# pCog100_Wifi_Sensor_uSD_TFT.net
KiCad netlist of a schematic drawn in EAGLE
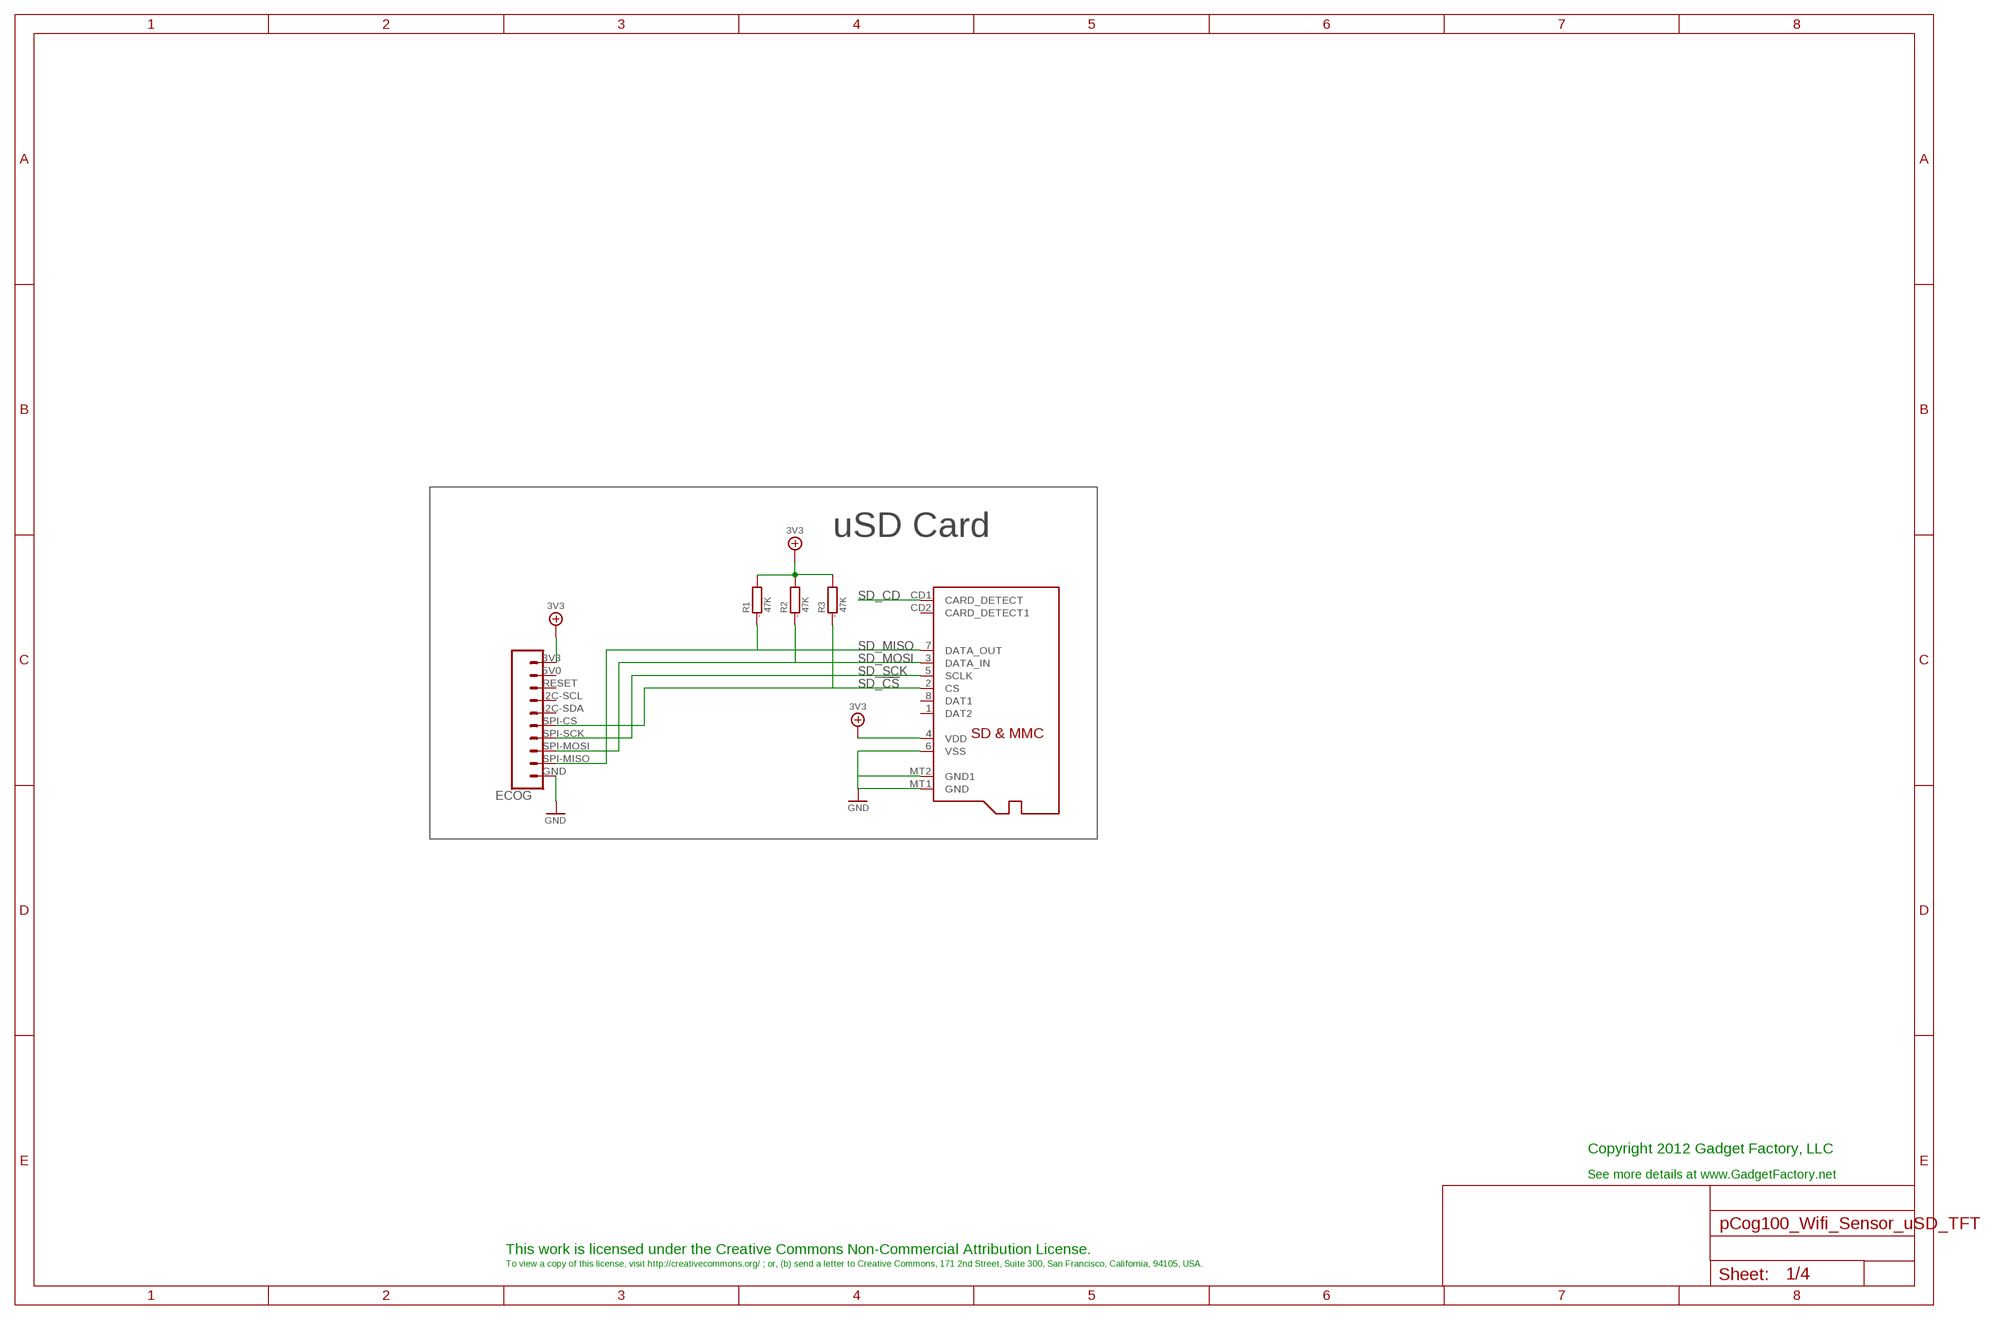
[diagram p0: schematic, sheet 1]
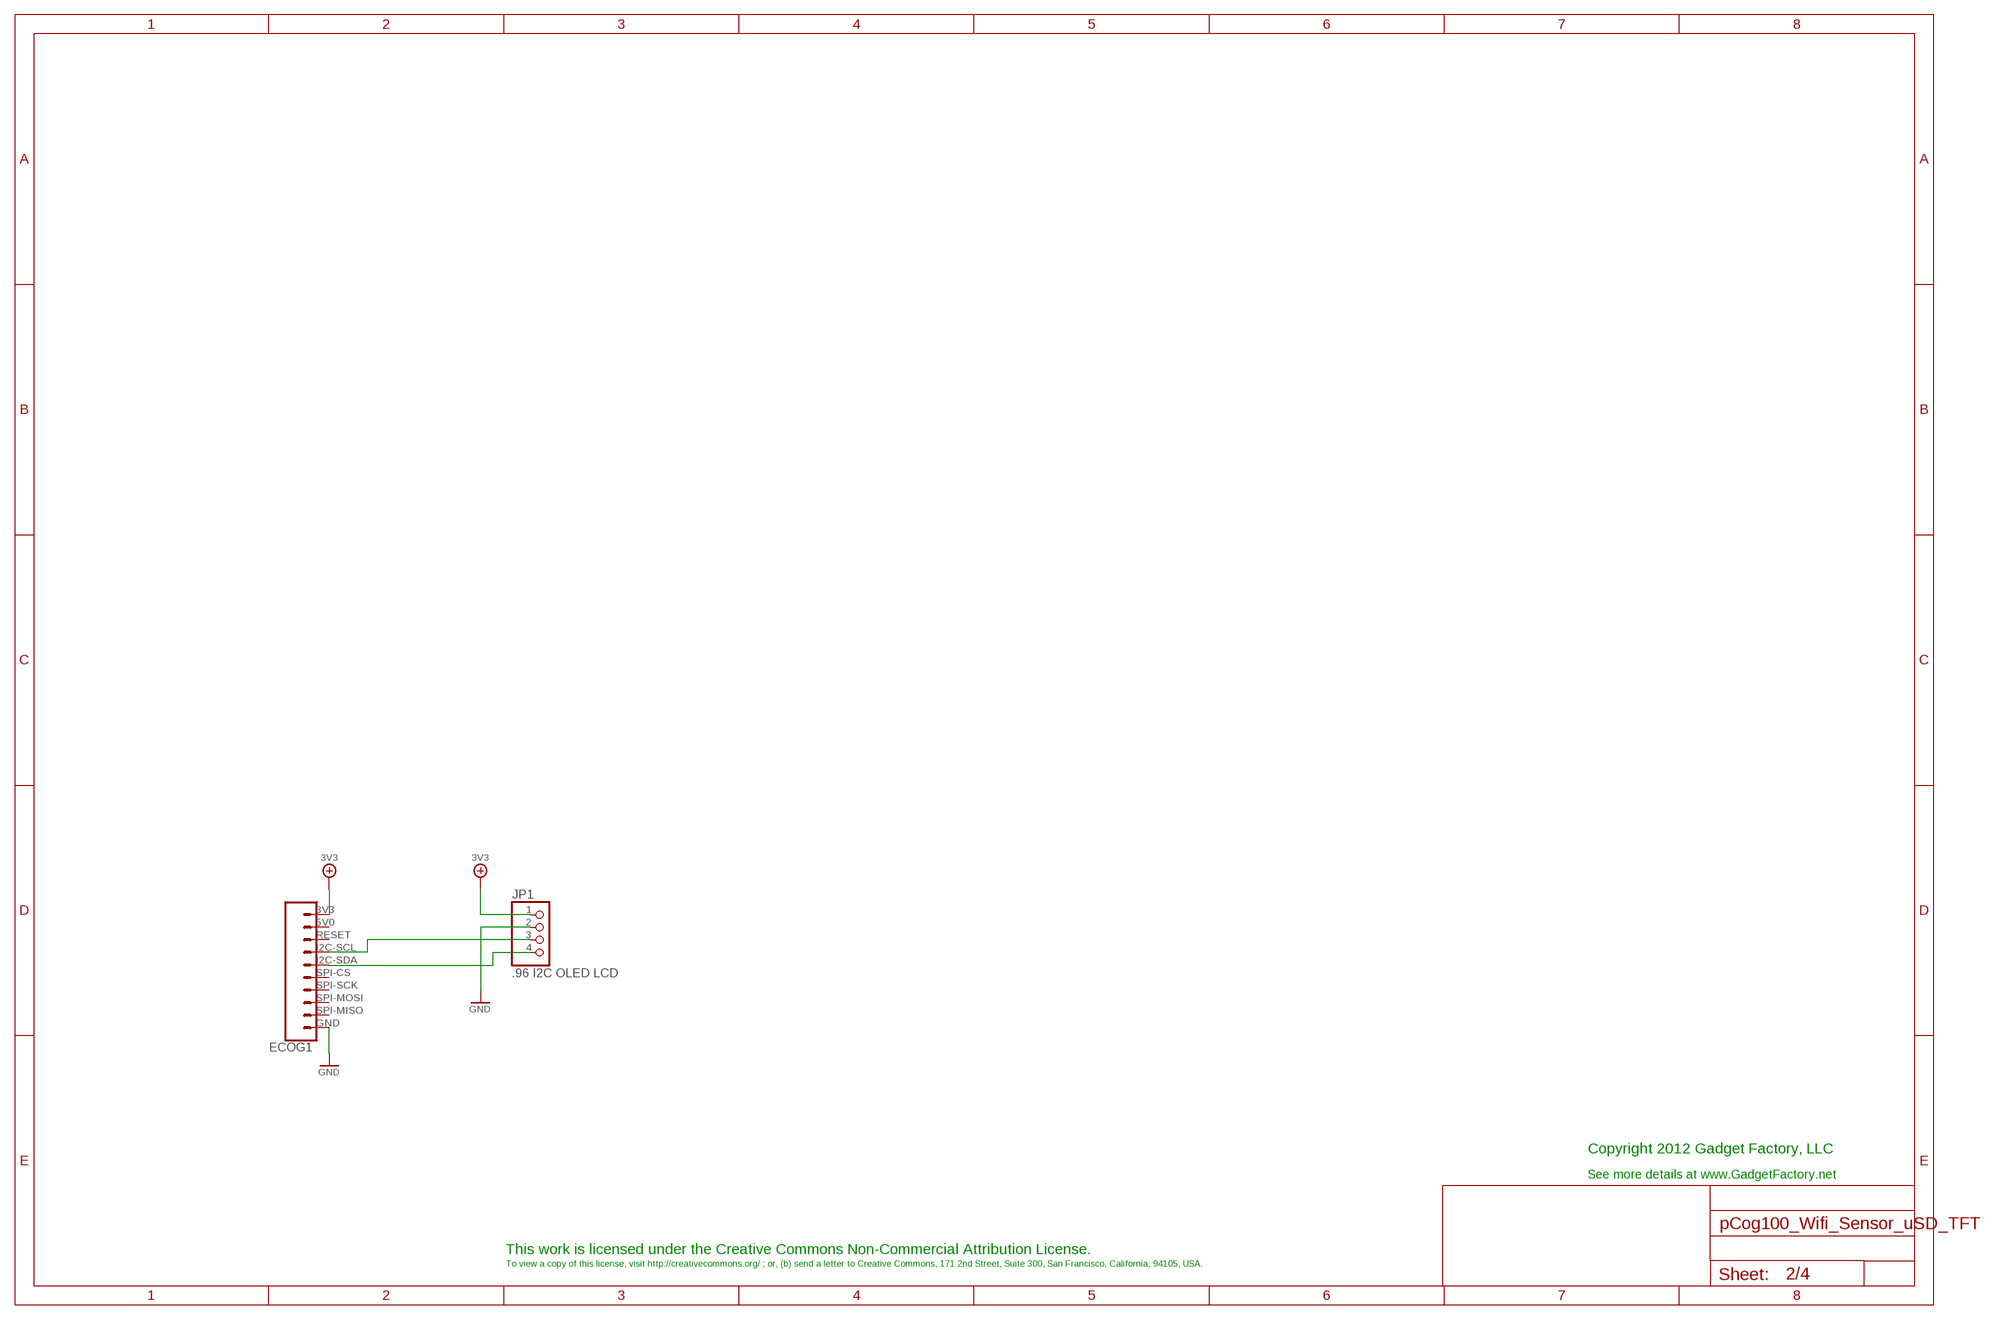
[diagram p1: schematic, sheet 2]
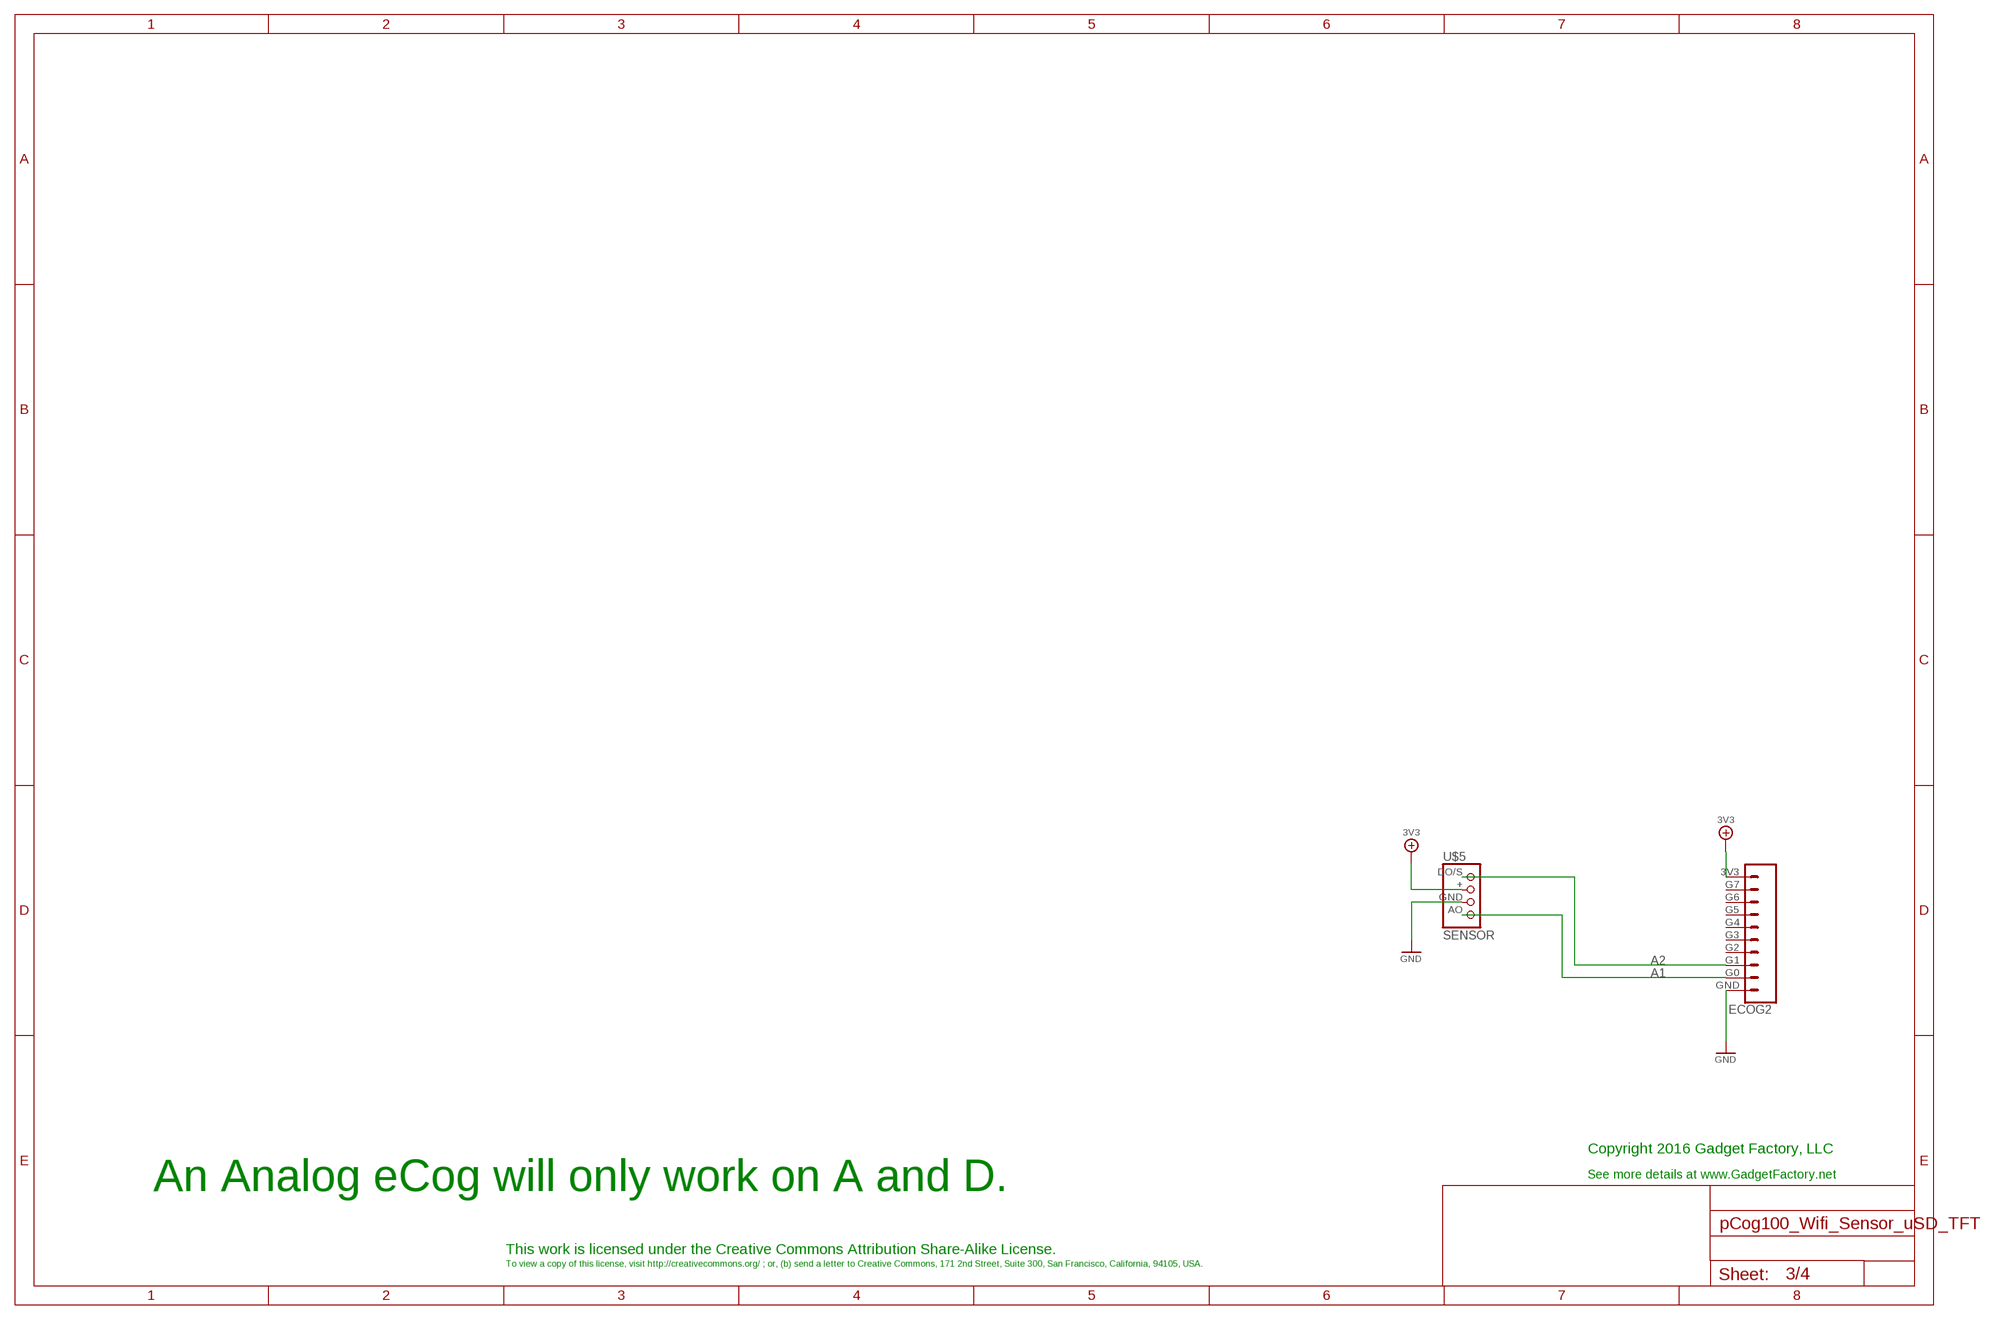
[diagram p2: schematic, sheet 3]
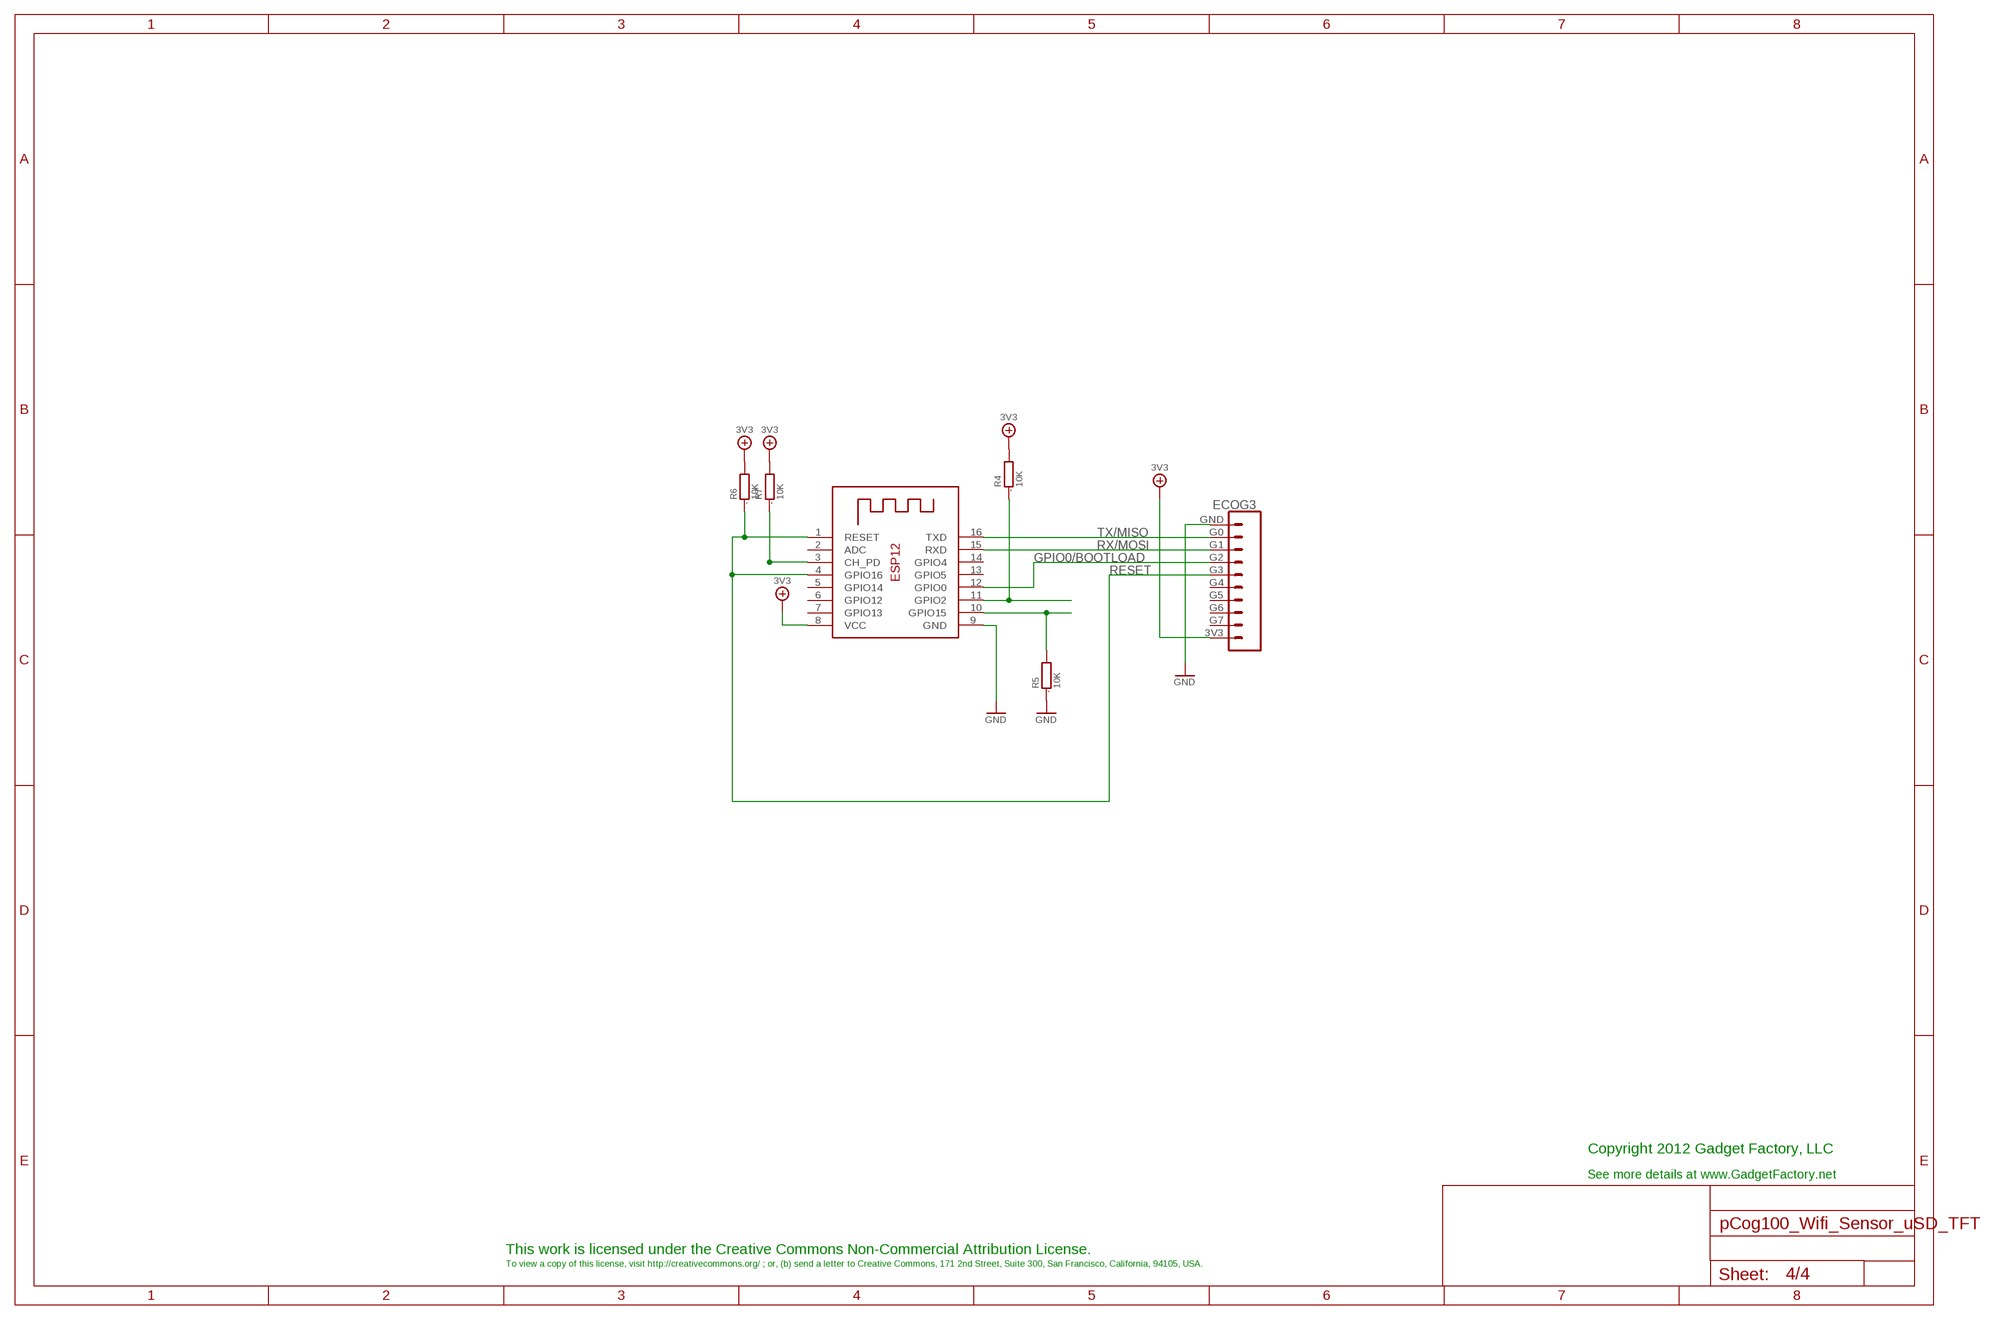
[diagram p3: schematic, sheet 4]

(export (version "E")
  (design (tool "Eeschema 10.0.6"))
  (components
    (comp (ref "ECOG2")
      (value "ECOG_GENERAL_ROWECOG_GENERAL_SMD")
      (footprint "eagle-import:ECOG_GENERAL_SMD")
      (libsource (lib "eagle-import") (part "ECOG_GENERAL_ROWECOG_GENERAL_SMD"))
    )
    (comp (ref "U$5")
      (value "SENSOR")
      (footprint "eagle-import:SENSOR-HJX4")
      (libsource (lib "eagle-import") (part "SENSOR"))
    )
    (comp (ref "ECOG3")
      (value "ECOG_GENERAL_ROWECOG_GENERAL_SMD")
      (footprint "eagle-import:ECOG_GENERAL_SMD")
      (libsource (lib "eagle-import") (part "ECOG_GENERAL_ROWECOG_GENERAL_SMD"))
    )
    (comp (ref "R4")
      (value "10K")
      (footprint "eagle-import:0805")
      (fields
        (field (name "PARTNO") "RC0805JR-0710KL,YAGEO (VA),dk,311-10KARCT-ND,RES SMD 10K OHM 5% 1/8W 0805, REF63")
      )
      (libsource (lib "eagle-import") (part "R0805"))
    )
    (comp (ref "R5")
      (value "10K")
      (footprint "eagle-import:0805")
      (fields
        (field (name "PARTNO") "RC0805JR-0710KL,YAGEO (VA),dk,311-10KARCT-ND,RES SMD 10K OHM 5% 1/8W 0805, REF63")
      )
      (libsource (lib "eagle-import") (part "R0805"))
    )
    (comp (ref "R6")
      (value "10K")
      (footprint "eagle-import:0805")
      (fields
        (field (name "PARTNO") "RC0805JR-0710KL,YAGEO (VA),dk,311-10KARCT-ND,RES SMD 10K OHM 5% 1/8W 0805, REF63")
      )
      (libsource (lib "eagle-import") (part "R0805"))
    )
    (comp (ref "R7")
      (value "10K")
      (footprint "eagle-import:0805")
      (fields
        (field (name "PARTNO") "RC0805JR-0710KL,YAGEO (VA),dk,311-10KARCT-ND,RES SMD 10K OHM 5% 1/8W 0805, REF63")
      )
      (libsource (lib "eagle-import") (part "R0805"))
    )
    (comp (ref "X1")
      (value "ESP-12")
      (footprint "eagle-import:ESP-12")
      (libsource (lib "eagle-import") (part "ESP-12"))
    )
    (comp (ref "ECOG1")
      (value "ECOG_BUSES_ROWECOG_BUSES_SMD")
      (footprint "eagle-import:ECOG_BUSES_SMD")
      (libsource (lib "eagle-import") (part "ECOG_BUSES_ROWECOG_BUSES_SMD"))
    )
    (comp (ref "JP1")
      (value ".96 I2C OLED LCD")
      (footprint "eagle-import:1X04")
      (libsource (lib "eagle-import") (part "PINHD-1X4"))
    )
    (comp (ref "ECOG")
      (value "ECOG_BUSES_ROWECOG_BUSES_SMD")
      (footprint "eagle-import:ECOG_BUSES_SMD")
      (libsource (lib "eagle-import") (part "ECOG_BUSES_ROWECOG_BUSES_SMD"))
    )
    (comp (ref "R1")
      (value "47K")
      (footprint "eagle-import:0805")
      (libsource (lib "eagle-import") (part "GadgetFactory_6.0_R0805"))
    )
    (comp (ref "R2")
      (value "47K")
      (footprint "eagle-import:0805")
      (libsource (lib "eagle-import") (part "GadgetFactory_6.0_R0805"))
    )
    (comp (ref "R3")
      (value "47K")
      (footprint "eagle-import:0805")
      (libsource (lib "eagle-import") (part "GadgetFactory_6.0_R0805"))
    )
    (comp (ref "SD1")
      (value "MICROSD")
      (footprint "eagle-import:MICROSD")
      (fields (field (name "DIGIKEY") "101-00660-68-6-1-ND"))
      (libsource (lib "eagle-import") (part "MICROSD"))
    )
  )
  (nets
    (net (code "1") (name "3V3") (class "Default")
      (node (ref "ECOG") (pin "3V3") (pinfunction "3V3_3V3") (pintype "passive"))
      (node (ref "ECOG1") (pin "3V3") (pinfunction "3V3_3V3") (pintype "passive"))
      (node (ref "ECOG2") (pin "3V3") (pinfunction "3V3_3V3") (pintype "power_in"))
      (node (ref "ECOG3") (pin "3V3") (pinfunction "3V3_3V3") (pintype "power_in"))
      (node (ref "JP1") (pin "1") (pinfunction "1_1") (pintype "passive"))
      (node (ref "R1") (pin "2") (pinfunction "2_2") (pintype "passive"))
      (node (ref "R2") (pin "2") (pinfunction "2_2") (pintype "passive"))
      (node (ref "R3") (pin "2") (pinfunction "2_2") (pintype "passive"))
      (node (ref "R4") (pin "2") (pinfunction "2_2") (pintype "passive"))
      (node (ref "R6") (pin "2") (pinfunction "2_2") (pintype "passive"))
      (node (ref "R7") (pin "2") (pinfunction "2_2") (pintype "passive"))
      (node (ref "SD1") (pin "4") (pinfunction "VDD_4") (pintype "power_in"))
      (node (ref "U$5") (pin "+") (pinfunction "+_+") (pintype "passive"))
      (node (ref "X1") (pin "8") (pinfunction "VCC_8") (pintype "power_in"))
    )
    (net (code "2") (name "A1") (class "Default")
      (node (ref "ECOG2") (pin "G0") (pinfunction "G0_G0") (pintype "passive"))
      (node (ref "U$5") (pin "AO") (pinfunction "AO_AO") (pintype "passive"))
    )
    (net (code "3") (name "A2") (class "Default")
      (node (ref "ECOG2") (pin "G1") (pinfunction "G1_G1") (pintype "passive"))
      (node (ref "U$5") (pin "DO/S") (pinfunction "DO/S_DO/S") (pintype "passive"))
    )
    (net (code "4") (name "GND") (class "Default")
      (node (ref "ECOG") (pin "GND") (pinfunction "GND_GND") (pintype "passive"))
      (node (ref "ECOG1") (pin "GND") (pinfunction "GND_GND") (pintype "passive"))
      (node (ref "ECOG2") (pin "GND") (pinfunction "GND_GND") (pintype "power_in"))
      (node (ref "ECOG3") (pin "GND") (pinfunction "GND_GND") (pintype "power_in"))
      (node (ref "JP1") (pin "2") (pinfunction "2_2") (pintype "passive"))
      (node (ref "R5") (pin "1") (pinfunction "1_1") (pintype "passive"))
      (node (ref "SD1") (pin "6") (pinfunction "VSS_6") (pintype "power_in"))
      (node (ref "SD1") (pin "MT1") (pinfunction "GND_MT1") (pintype "power_in"))
      (node (ref "SD1") (pin "MT2") (pinfunction "GND1_MT2") (pintype "power_in"))
      (node (ref "U$5") (pin "GND") (pinfunction "GND_GND") (pintype "passive"))
      (node (ref "X1") (pin "9") (pinfunction "GND_9") (pintype "power_in"))
    )
    (net (code "5") (name "GPIO0{slash}BOOTLOAD") (class "Default")
      (node (ref "ECOG3") (pin "G2") (pinfunction "G2_G2") (pintype "passive"))
      (node (ref "X1") (pin "12") (pinfunction "GPIO0_12") (pintype "bidirectional"))
    )
    (net (code "6") (name "Net-(ECOG1-PadI2C-SCL)") (class "Default")
      (node (ref "ECOG1") (pin "I2C-SCL") (pinfunction "I2C-SCL_I2C-SCL") (pintype "passive"))
      (node (ref "JP1") (pin "3") (pinfunction "3_3") (pintype "passive"))
    )
    (net (code "7") (name "Net-(ECOG1-PadI2C-SDA)") (class "Default")
      (node (ref "ECOG1") (pin "I2C-SDA") (pinfunction "I2C-SDA_I2C-SDA") (pintype "passive"))
      (node (ref "JP1") (pin "4") (pinfunction "4_4") (pintype "passive"))
    )
    (net (code "8") (name "Net-(X1-CH_PD)") (class "Default")
      (node (ref "R7") (pin "1") (pinfunction "1_1") (pintype "passive"))
      (node (ref "X1") (pin "3") (pinfunction "CH_PD_3") (pintype "input"))
    )
    (net (code "9") (name "Net-(X1-GPIO2)") (class "Default")
      (node (ref "R4") (pin "1") (pinfunction "1_1") (pintype "passive"))
      (node (ref "X1") (pin "11") (pinfunction "GPIO2_11") (pintype "bidirectional"))
    )
    (net (code "10") (name "Net-(X1-GPIO15)") (class "Default")
      (node (ref "R5") (pin "2") (pinfunction "2_2") (pintype "passive"))
      (node (ref "X1") (pin "10") (pinfunction "GPIO15_10") (pintype "bidirectional"))
    )
    (net (code "11") (name "RESET") (class "Default")
      (node (ref "ECOG3") (pin "G3") (pinfunction "G3_G3") (pintype "passive"))
      (node (ref "R6") (pin "1") (pinfunction "1_1") (pintype "passive"))
      (node (ref "X1") (pin "1") (pinfunction "RESET_1") (pintype "input"))
      (node (ref "X1") (pin "4") (pinfunction "GPIO16_4") (pintype "bidirectional"))
    )
    (net (code "12") (name "RX{slash}MOSI") (class "Default")
      (node (ref "ECOG3") (pin "G1") (pinfunction "G1_G1") (pintype "passive"))
      (node (ref "X1") (pin "15") (pinfunction "RXD_15") (pintype "input"))
    )
    (net (code "13") (name "SD_CD") (class "Default")
      (node (ref "SD1") (pin "CD1") (pinfunction "CARD_DETECT_CD1") (pintype "passive"))
    )
    (net (code "14") (name "SD_MISO") (class "Default")
      (node (ref "ECOG") (pin "SPI-MISO") (pinfunction "SPI-MISO_SPI-MISO") (pintype "passive"))
      (node (ref "R1") (pin "1") (pinfunction "1_1") (pintype "passive"))
      (node (ref "SD1") (pin "7") (pinfunction "DATA_OUT_7") (pintype "output"))
    )
    (net (code "15") (name "SD_MOSI") (class "Default")
      (node (ref "ECOG") (pin "SPI-MOSI") (pinfunction "SPI-MOSI_SPI-MOSI") (pintype "passive"))
      (node (ref "R2") (pin "1") (pinfunction "1_1") (pintype "passive"))
      (node (ref "SD1") (pin "3") (pinfunction "DATA_IN_3") (pintype "input"))
    )
    (net (code "16") (name "SD_SCK") (class "Default")
      (node (ref "ECOG") (pin "SPI-SCK") (pinfunction "SPI-SCK_SPI-SCK") (pintype "passive"))
      (node (ref "SD1") (pin "5") (pinfunction "SCLK_5") (pintype "input"))
    )
    (net (code "17") (name "SD_~{CS}") (class "Default")
      (node (ref "ECOG") (pin "SPI-CS") (pinfunction "SPI-CS_SPI-CS") (pintype "passive"))
      (node (ref "R3") (pin "1") (pinfunction "1_1") (pintype "passive"))
      (node (ref "SD1") (pin "2") (pinfunction "CS_2") (pintype "input"))
    )
    (net (code "18") (name "TX{slash}MISO") (class "Default")
      (node (ref "ECOG3") (pin "G0") (pinfunction "G0_G0") (pintype "passive"))
      (node (ref "X1") (pin "16") (pinfunction "TXD_16") (pintype "output"))
    )
    (net (code "19") (name "unconnected-(ECOG-Pad5V0)") (class "Default")
      (node (ref "ECOG") (pin "5V0") (pinfunction "5V0_5V0") (pintype "passive"))
    )
    (net (code "20") (name "unconnected-(ECOG-PadI2C-SCL)") (class "Default")
      (node (ref "ECOG") (pin "I2C-SCL") (pinfunction "I2C-SCL_I2C-SCL") (pintype "passive"))
    )
    (net (code "21") (name "unconnected-(ECOG-PadI2C-SDA)") (class "Default")
      (node (ref "ECOG") (pin "I2C-SDA") (pinfunction "I2C-SDA_I2C-SDA") (pintype "passive"))
    )
    (net (code "22") (name "unconnected-(ECOG-PadRESET)") (class "Default")
      (node (ref "ECOG") (pin "RESET") (pinfunction "RESET_RESET") (pintype "passive"))
    )
    (net (code "23") (name "unconnected-(ECOG1-Pad5V0)") (class "Default")
      (node (ref "ECOG1") (pin "5V0") (pinfunction "5V0_5V0") (pintype "passive"))
    )
    (net (code "24") (name "unconnected-(ECOG1-PadRESET)") (class "Default")
      (node (ref "ECOG1") (pin "RESET") (pinfunction "RESET_RESET") (pintype "passive"))
    )
    (net (code "25") (name "unconnected-(ECOG1-PadSPI-CS)") (class "Default")
      (node (ref "ECOG1") (pin "SPI-CS") (pinfunction "SPI-CS_SPI-CS") (pintype "passive"))
    )
    (net (code "26") (name "unconnected-(ECOG1-PadSPI-MISO)") (class "Default")
      (node (ref "ECOG1") (pin "SPI-MISO") (pinfunction "SPI-MISO_SPI-MISO") (pintype "passive"))
    )
    (net (code "27") (name "unconnected-(ECOG1-PadSPI-MOSI)") (class "Default")
      (node (ref "ECOG1") (pin "SPI-MOSI") (pinfunction "SPI-MOSI_SPI-MOSI") (pintype "passive"))
    )
    (net (code "28") (name "unconnected-(ECOG1-PadSPI-SCK)") (class "Default")
      (node (ref "ECOG1") (pin "SPI-SCK") (pinfunction "SPI-SCK_SPI-SCK") (pintype "passive"))
    )
    (net (code "29") (name "unconnected-(ECOG2-PadG2)") (class "Default")
      (node (ref "ECOG2") (pin "G2") (pinfunction "G2_G2") (pintype "passive"))
    )
    (net (code "30") (name "unconnected-(ECOG2-PadG3)") (class "Default")
      (node (ref "ECOG2") (pin "G3") (pinfunction "G3_G3") (pintype "passive"))
    )
    (net (code "31") (name "unconnected-(ECOG2-PadG4)") (class "Default")
      (node (ref "ECOG2") (pin "G4") (pinfunction "G4_G4") (pintype "passive"))
    )
    (net (code "32") (name "unconnected-(ECOG2-PadG5)") (class "Default")
      (node (ref "ECOG2") (pin "G5") (pinfunction "G5_G5") (pintype "passive"))
    )
    (net (code "33") (name "unconnected-(ECOG2-PadG6)") (class "Default")
      (node (ref "ECOG2") (pin "G6") (pinfunction "G6_G6") (pintype "passive"))
    )
    (net (code "34") (name "unconnected-(ECOG2-PadG7)") (class "Default")
      (node (ref "ECOG2") (pin "G7") (pinfunction "G7_G7") (pintype "passive"))
    )
    (net (code "35") (name "unconnected-(ECOG3-PadG4)") (class "Default")
      (node (ref "ECOG3") (pin "G4") (pinfunction "G4_G4") (pintype "passive"))
    )
    (net (code "36") (name "unconnected-(ECOG3-PadG5)") (class "Default")
      (node (ref "ECOG3") (pin "G5") (pinfunction "G5_G5") (pintype "passive"))
    )
    (net (code "37") (name "unconnected-(ECOG3-PadG6)") (class "Default")
      (node (ref "ECOG3") (pin "G6") (pinfunction "G6_G6") (pintype "passive"))
    )
    (net (code "38") (name "unconnected-(ECOG3-PadG7)") (class "Default")
      (node (ref "ECOG3") (pin "G7") (pinfunction "G7_G7") (pintype "passive"))
    )
    (net (code "39") (name "unconnected-(SD1-CARD_DETECT1-PadCD2)") (class "Default")
      (node (ref "SD1") (pin "CD2") (pinfunction "CARD_DETECT1_CD2") (pintype "passive"))
    )
    (net (code "40") (name "unconnected-(SD1-DAT1-Pad8)") (class "Default")
      (node (ref "SD1") (pin "8") (pinfunction "DAT1_8") (pintype "bidirectional"))
    )
    (net (code "41") (name "unconnected-(SD1-DAT2-Pad1)") (class "Default")
      (node (ref "SD1") (pin "1") (pinfunction "DAT2_1") (pintype "bidirectional"))
    )
    (net (code "42") (name "unconnected-(X1-ADC-Pad2)") (class "Default")
      (node (ref "X1") (pin "2") (pinfunction "ADC_2") (pintype "passive"))
    )
    (net (code "43") (name "unconnected-(X1-GPIO4-Pad14)") (class "Default")
      (node (ref "X1") (pin "14") (pinfunction "GPIO4_14") (pintype "bidirectional"))
    )
    (net (code "44") (name "unconnected-(X1-GPIO5-Pad13)") (class "Default")
      (node (ref "X1") (pin "13") (pinfunction "GPIO5_13") (pintype "bidirectional"))
    )
    (net (code "45") (name "unconnected-(X1-GPIO12-Pad6)") (class "Default")
      (node (ref "X1") (pin "6") (pinfunction "GPIO12_6") (pintype "bidirectional"))
    )
    (net (code "46") (name "unconnected-(X1-GPIO13-Pad7)") (class "Default")
      (node (ref "X1") (pin "7") (pinfunction "GPIO13_7") (pintype "bidirectional"))
    )
    (net (code "47") (name "unconnected-(X1-GPIO14-Pad5)") (class "Default")
      (node (ref "X1") (pin "5") (pinfunction "GPIO14_5") (pintype "bidirectional"))
    )
  )
)
